# OV7670.net
KiCad netlist of a schematic drawn in EAGLE
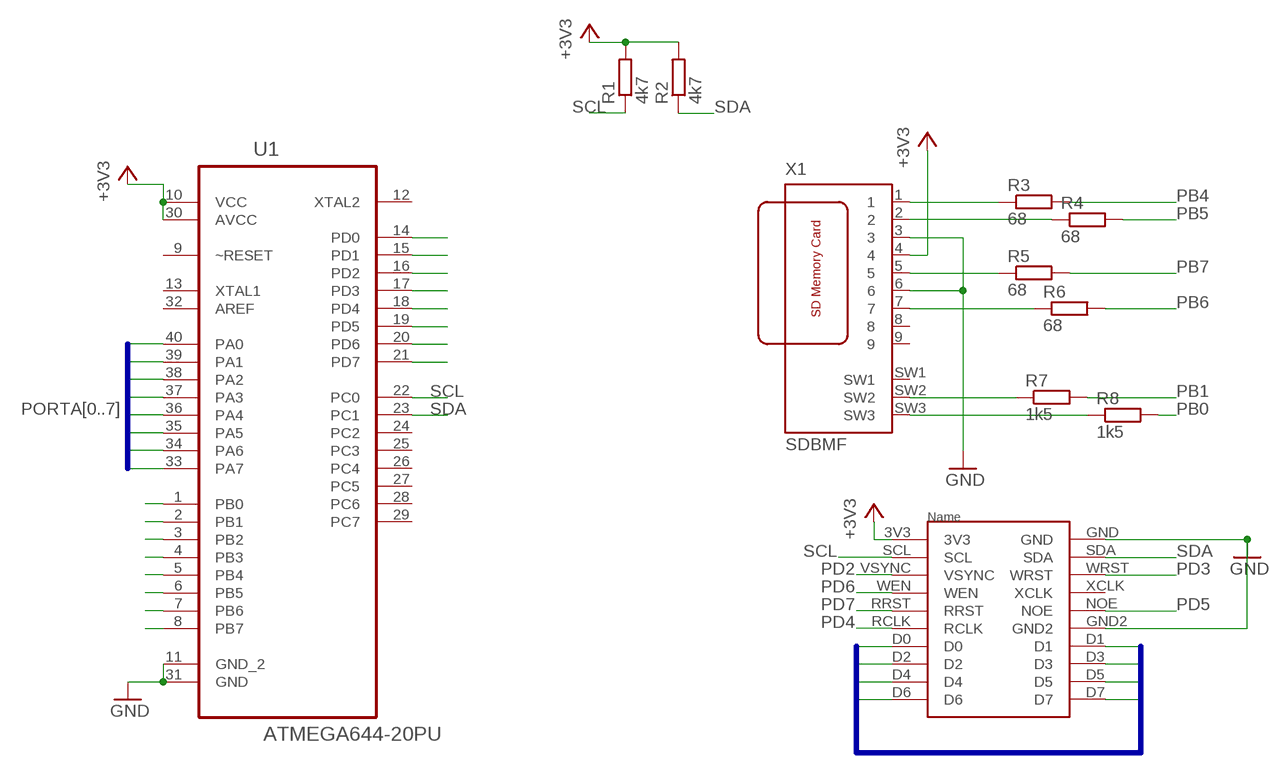
[diagram p0: schematic, sheet 1]

(export (version "E")
  (design (tool "Eeschema 10.0.6"))
  (components
    (comp (ref "OV7670")
      (value "OV7670")
      (footprint "eagle-import:OV7670")
      (libsource (lib "eagle-import") (part "OV7670"))
    )
    (comp (ref "R1")
      (value "4k7")
      (footprint "eagle-import:0204_5")
      (libsource (lib "eagle-import") (part "R-EU_0204/5"))
    )
    (comp (ref "R2")
      (value "4k7")
      (footprint "eagle-import:0204_5")
      (libsource (lib "eagle-import") (part "R-EU_0204/5"))
    )
    (comp (ref "R3")
      (value "68")
      (footprint "eagle-import:0204_5")
      (libsource (lib "eagle-import") (part "R-EU_0204/5"))
    )
    (comp (ref "R4")
      (value "68")
      (footprint "eagle-import:0204_5")
      (libsource (lib "eagle-import") (part "R-EU_0204/5"))
    )
    (comp (ref "R5")
      (value "68")
      (footprint "eagle-import:0204_5")
      (libsource (lib "eagle-import") (part "R-EU_0204/5"))
    )
    (comp (ref "R6")
      (value "68")
      (footprint "eagle-import:0204_5")
      (libsource (lib "eagle-import") (part "R-EU_0204/5"))
    )
    (comp (ref "R7")
      (value "1k5")
      (footprint "eagle-import:0204_5")
      (libsource (lib "eagle-import") (part "R-EU_0204/5"))
    )
    (comp (ref "R8")
      (value "1k5")
      (footprint "eagle-import:0204_5")
      (libsource (lib "eagle-import") (part "R-EU_0204/5"))
    )
    (comp (ref "U1")
      (value "ATMEGA644-20PU")
      (footprint "eagle-import:DIP254P1524X482-40")
      (libsource (lib "eagle-import") (part "ATMEGA644-20PU"))
    )
    (comp (ref "X1")
      (value "SDBMF")
      (footprint "eagle-import:SDBMF-009XXBXX2")
      (libsource (lib "eagle-import") (part "SDBMF"))
    )
  )
  (nets
    (net (code "2") (name "+3V3") (class "Default")
      (node (ref "OV7670") (pin "3V3") (pinfunction "3V3_3V3") (pintype "power_in"))
      (node (ref "R1") (pin "2") (pinfunction "2_2") (pintype "passive"))
      (node (ref "R2") (pin "2") (pinfunction "2_2") (pintype "passive"))
      (node (ref "U1") (pin "10") (pinfunction "VCC_10") (pintype "power_in"))
      (node (ref "U1") (pin "30") (pinfunction "AVCC_30") (pintype "power_in"))
      (node (ref "X1") (pin "4") (pinfunction "4_4") (pintype "passive"))
    )
    (net (code "3") (name "/PB0") (class "Default")
      (node (ref "R8") (pin "2") (pinfunction "2_2") (pintype "passive"))
      (node (ref "U1") (pin "1") (pinfunction "PB0_1") (pintype "bidirectional"))
    )
    (net (code "4") (name "/PB1") (class "Default")
      (node (ref "R7") (pin "2") (pinfunction "2_2") (pintype "passive"))
      (node (ref "U1") (pin "2") (pinfunction "PB1_2") (pintype "bidirectional"))
    )
    (net (code "5") (name "/PB4") (class "Default")
      (node (ref "R3") (pin "2") (pinfunction "2_2") (pintype "passive"))
      (node (ref "U1") (pin "5") (pinfunction "PB4_5") (pintype "bidirectional"))
    )
    (net (code "6") (name "/PB5") (class "Default")
      (node (ref "R4") (pin "2") (pinfunction "2_2") (pintype "passive"))
      (node (ref "U1") (pin "6") (pinfunction "PB5_6") (pintype "bidirectional"))
    )
    (net (code "7") (name "/PB6") (class "Default")
      (node (ref "R6") (pin "2") (pinfunction "2_2") (pintype "passive"))
      (node (ref "U1") (pin "7") (pinfunction "PB6_7") (pintype "bidirectional"))
    )
    (net (code "8") (name "/PB7") (class "Default")
      (node (ref "R5") (pin "2") (pinfunction "2_2") (pintype "passive"))
      (node (ref "U1") (pin "8") (pinfunction "PB7_8") (pintype "bidirectional"))
    )
    (net (code "9") (name "/PD2") (class "Default")
      (node (ref "OV7670") (pin "VSYNC") (pinfunction "VSYNC_VSYNC") (pintype "output"))
      (node (ref "U1") (pin "16") (pinfunction "PD2_16") (pintype "bidirectional"))
    )
    (net (code "10") (name "/PD3") (class "Default")
      (node (ref "OV7670") (pin "WRST") (pinfunction "WRST_WRST") (pintype "input"))
      (node (ref "U1") (pin "17") (pinfunction "PD3_17") (pintype "bidirectional"))
    )
    (net (code "11") (name "/PD4") (class "Default")
      (node (ref "OV7670") (pin "RCLK") (pinfunction "RCLK_RCLK") (pintype "input"))
      (node (ref "U1") (pin "18") (pinfunction "PD4_18") (pintype "bidirectional"))
    )
    (net (code "12") (name "/PD5") (class "Default")
      (node (ref "OV7670") (pin "NOE") (pinfunction "NOE_NOE") (pintype "input"))
      (node (ref "U1") (pin "19") (pinfunction "PD5_19") (pintype "bidirectional"))
    )
    (net (code "13") (name "/PD6") (class "Default")
      (node (ref "OV7670") (pin "WEN") (pinfunction "WEN_WEN") (pintype "input"))
      (node (ref "U1") (pin "20") (pinfunction "PD6_20") (pintype "bidirectional"))
    )
    (net (code "14") (name "/PD7") (class "Default")
      (node (ref "OV7670") (pin "RRST") (pinfunction "RRST_RRST") (pintype "input"))
      (node (ref "U1") (pin "21") (pinfunction "PD7_21") (pintype "bidirectional"))
    )
    (net (code "15") (name "/PORTA0") (class "Default")
      (node (ref "OV7670") (pin "D0") (pinfunction "D0_D0") (pintype "output"))
      (node (ref "U1") (pin "40") (pinfunction "PA0_40") (pintype "bidirectional"))
    )
    (net (code "16") (name "/PORTA1") (class "Default")
      (node (ref "OV7670") (pin "D1") (pinfunction "D1_D1") (pintype "output"))
      (node (ref "U1") (pin "39") (pinfunction "PA1_39") (pintype "bidirectional"))
    )
    (net (code "17") (name "/PORTA2") (class "Default")
      (node (ref "OV7670") (pin "D2") (pinfunction "D2_D2") (pintype "output"))
      (node (ref "U1") (pin "38") (pinfunction "PA2_38") (pintype "bidirectional"))
    )
    (net (code "18") (name "/PORTA3") (class "Default")
      (node (ref "OV7670") (pin "D3") (pinfunction "D3_D3") (pintype "output"))
      (node (ref "U1") (pin "37") (pinfunction "PA3_37") (pintype "bidirectional"))
    )
    (net (code "19") (name "/PORTA4") (class "Default")
      (node (ref "OV7670") (pin "D4") (pinfunction "D4_D4") (pintype "output"))
      (node (ref "U1") (pin "36") (pinfunction "PA4_36") (pintype "bidirectional"))
    )
    (net (code "20") (name "/PORTA5") (class "Default")
      (node (ref "OV7670") (pin "D5") (pinfunction "D5_D5") (pintype "output"))
      (node (ref "U1") (pin "35") (pinfunction "PA5_35") (pintype "bidirectional"))
    )
    (net (code "21") (name "/PORTA6") (class "Default")
      (node (ref "OV7670") (pin "D6") (pinfunction "D6_D6") (pintype "output"))
      (node (ref "U1") (pin "34") (pinfunction "PA6_34") (pintype "bidirectional"))
    )
    (net (code "23") (name "/SCL") (class "Default")
      (node (ref "OV7670") (pin "SCL") (pinfunction "SCL_SCL") (pintype "input"))
      (node (ref "R1") (pin "1") (pinfunction "1_1") (pintype "passive"))
      (node (ref "U1") (pin "22") (pinfunction "PC0_22") (pintype "bidirectional"))
    )
    (net (code "24") (name "/SDA") (class "Default")
      (node (ref "OV7670") (pin "SDA") (pinfunction "SDA_SDA") (pintype "bidirectional"))
      (node (ref "R2") (pin "1") (pinfunction "1_1") (pintype "passive"))
      (node (ref "U1") (pin "23") (pinfunction "PC1_23") (pintype "bidirectional"))
    )
    (net (code "25") (name "GND") (class "Default")
      (node (ref "OV7670") (pin "GND") (pinfunction "GND_GND") (pintype "power_in"))
      (node (ref "OV7670") (pin "GND2") (pinfunction "GND2_GND2") (pintype "power_in"))
      (node (ref "U1") (pin "11") (pinfunction "GND_2_11") (pintype "passive"))
      (node (ref "U1") (pin "31") (pinfunction "GND_31") (pintype "passive"))
      (node (ref "X1") (pin "3") (pinfunction "3_3") (pintype "passive"))
      (node (ref "X1") (pin "6") (pinfunction "6_6") (pintype "passive"))
    )
    (net (code "26") (name "Net-(R3-Pad1)") (class "Default")
      (node (ref "R3") (pin "1") (pinfunction "1_1") (pintype "passive"))
      (node (ref "X1") (pin "1") (pinfunction "1_1") (pintype "passive"))
    )
    (net (code "27") (name "Net-(R4-Pad1)") (class "Default")
      (node (ref "R4") (pin "1") (pinfunction "1_1") (pintype "passive"))
      (node (ref "X1") (pin "2") (pinfunction "2_2") (pintype "passive"))
    )
    (net (code "28") (name "Net-(R5-Pad1)") (class "Default")
      (node (ref "R5") (pin "1") (pinfunction "1_1") (pintype "passive"))
      (node (ref "X1") (pin "5") (pinfunction "5_5") (pintype "passive"))
    )
    (net (code "29") (name "Net-(R6-Pad1)") (class "Default")
      (node (ref "R6") (pin "1") (pinfunction "1_1") (pintype "passive"))
      (node (ref "X1") (pin "7") (pinfunction "7_7") (pintype "passive"))
    )
    (net (code "30") (name "Net-(R7-Pad1)") (class "Default")
      (node (ref "R7") (pin "1") (pinfunction "1_1") (pintype "passive"))
      (node (ref "X1") (pin "SW2") (pinfunction "SW2_SW2") (pintype "passive"))
    )
    (net (code "31") (name "Net-(R8-Pad1)") (class "Default")
      (node (ref "R8") (pin "1") (pinfunction "1_1") (pintype "passive"))
      (node (ref "X1") (pin "SW3") (pinfunction "SW3_SW3") (pintype "passive"))
    )
    (net (code "32") (name "unconnected-(OV7670-PadD7)") (class "Default")
      (node (ref "OV7670") (pin "D7") (pinfunction "D7_D7") (pintype "output"))
    )
    (net (code "33") (name "unconnected-(OV7670-PadXCLK)") (class "Default")
      (node (ref "OV7670") (pin "XCLK") (pinfunction "XCLK_XCLK") (pintype "output"))
    )
    (net (code "34") (name "unconnected-(U1-AREF-Pad32)") (class "Default")
      (node (ref "U1") (pin "32") (pinfunction "AREF_32") (pintype "input"))
    )
    (net (code "35") (name "unconnected-(U1-PA7-Pad33)") (class "Default")
      (node (ref "U1") (pin "33") (pinfunction "PA7_33") (pintype "bidirectional"))
    )
    (net (code "36") (name "unconnected-(U1-PB2-Pad3)") (class "Default")
      (node (ref "U1") (pin "3") (pinfunction "PB2_3") (pintype "bidirectional"))
    )
    (net (code "37") (name "unconnected-(U1-PB3-Pad4)") (class "Default")
      (node (ref "U1") (pin "4") (pinfunction "PB3_4") (pintype "bidirectional"))
    )
    (net (code "38") (name "unconnected-(U1-PC2-Pad24)") (class "Default")
      (node (ref "U1") (pin "24") (pinfunction "PC2_24") (pintype "bidirectional"))
    )
    (net (code "39") (name "unconnected-(U1-PC3-Pad25)") (class "Default")
      (node (ref "U1") (pin "25") (pinfunction "PC3_25") (pintype "bidirectional"))
    )
    (net (code "40") (name "unconnected-(U1-PC4-Pad26)") (class "Default")
      (node (ref "U1") (pin "26") (pinfunction "PC4_26") (pintype "bidirectional"))
    )
    (net (code "41") (name "unconnected-(U1-PC5-Pad27)") (class "Default")
      (node (ref "U1") (pin "27") (pinfunction "PC5_27") (pintype "bidirectional"))
    )
    (net (code "42") (name "unconnected-(U1-PC6-Pad28)") (class "Default")
      (node (ref "U1") (pin "28") (pinfunction "PC6_28") (pintype "bidirectional"))
    )
    (net (code "43") (name "unconnected-(U1-PC7-Pad29)") (class "Default")
      (node (ref "U1") (pin "29") (pinfunction "PC7_29") (pintype "bidirectional"))
    )
    (net (code "44") (name "unconnected-(U1-PD0-Pad14)") (class "Default")
      (node (ref "U1") (pin "14") (pinfunction "PD0_14") (pintype "bidirectional"))
    )
    (net (code "45") (name "unconnected-(U1-PD1-Pad15)") (class "Default")
      (node (ref "U1") (pin "15") (pinfunction "PD1_15") (pintype "bidirectional"))
    )
    (net (code "46") (name "unconnected-(U1-XTAL1-Pad13)") (class "Default")
      (node (ref "U1") (pin "13") (pinfunction "XTAL1_13") (pintype "input"))
    )
    (net (code "47") (name "unconnected-(U1-XTAL2-Pad12)") (class "Default")
      (node (ref "U1") (pin "12") (pinfunction "XTAL2_12") (pintype "output"))
    )
    (net (code "48") (name "unconnected-(U1-~{RESET}-Pad9)") (class "Default")
      (node (ref "U1") (pin "9") (pinfunction "~{RESET}_9") (pintype "input"))
    )
    (net (code "49") (name "unconnected-(X1-Pad8)") (class "Default")
      (node (ref "X1") (pin "8") (pinfunction "8_8") (pintype "passive"))
    )
    (net (code "50") (name "unconnected-(X1-Pad9)") (class "Default")
      (node (ref "X1") (pin "9") (pinfunction "9_9") (pintype "passive"))
    )
    (net (code "51") (name "unconnected-(X1-PadSW1)") (class "Default")
      (node (ref "X1") (pin "SW1") (pinfunction "SW1_SW1") (pintype "passive"))
    )
  )
)
